# Audio_Power.net
KiCad netlist of a schematic drawn in Altium Designer
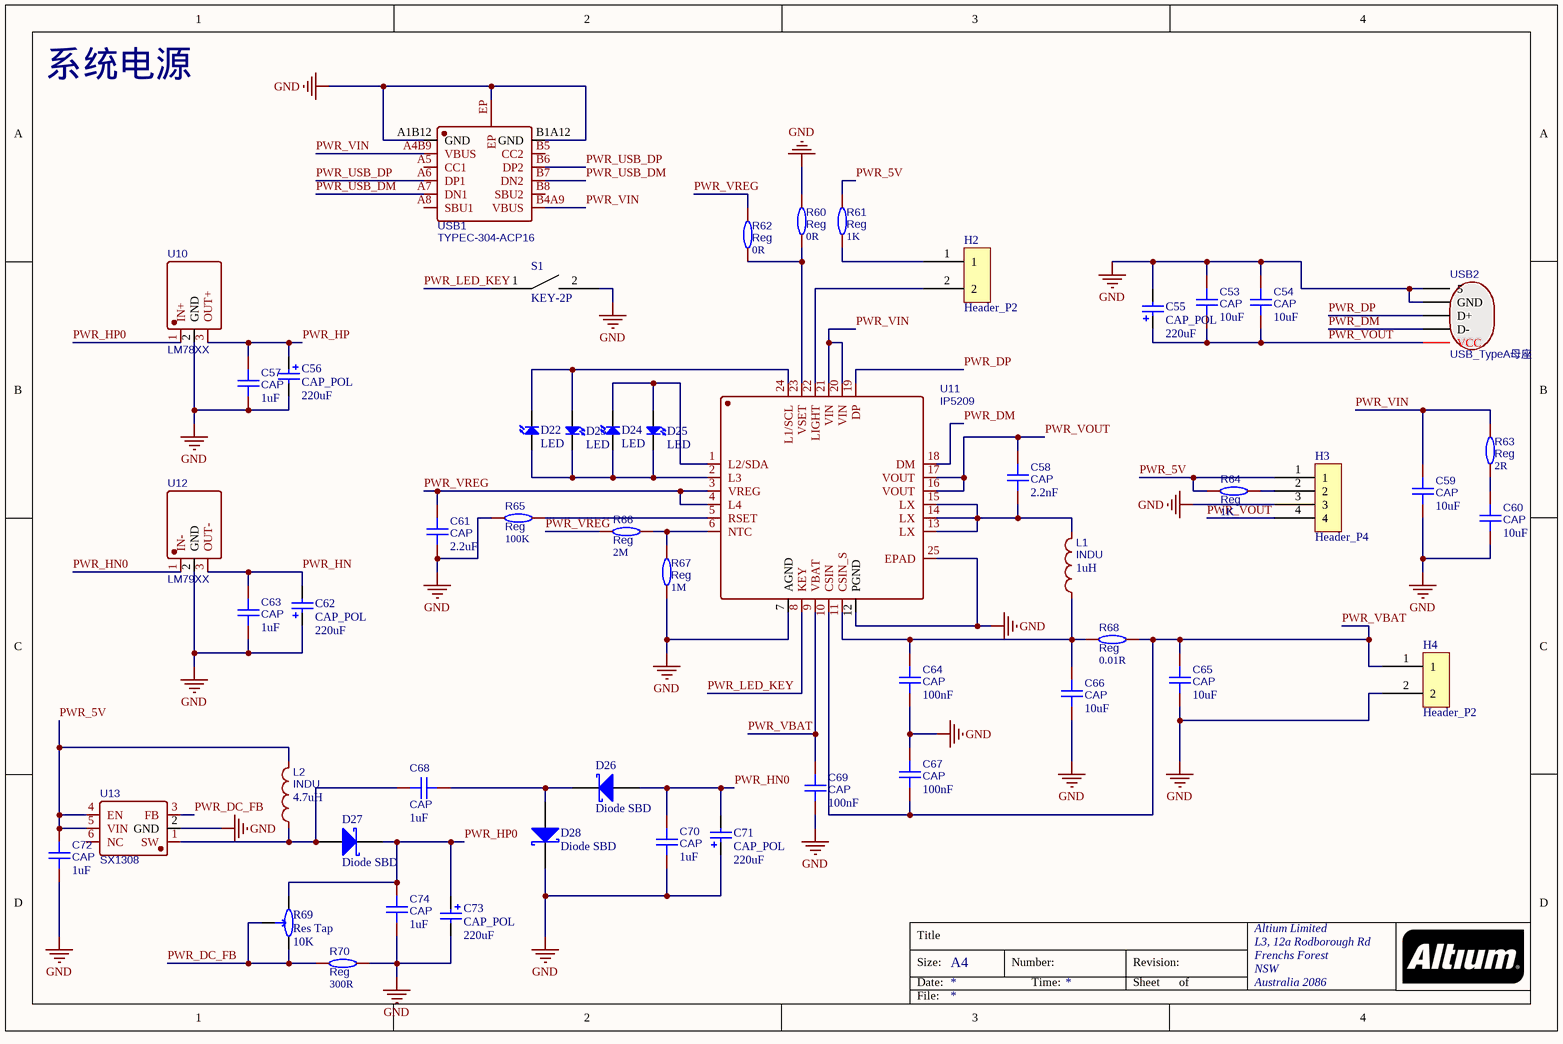
[diagram p0: Audio_Power.SchDoc]

(export (version "E")
  (design (tool "Eeschema 10.0.6"))
  (components
    (comp (ref "C53")
      (value "CAP")
      (footprint "C0603")
      (description "Cap")
      (fields
        (field (name "BOM_SUPPLIER PART") "C302008")
        (field (name "BOM_MANUFACTURER PART") "0603B103K101CT")
        (field (name "ALTIUM_VALUE") "10uF")
        (field (name "CONTRIBUTOR") "LCSC")
      )
      (libsource (lib "Levent_lib") (part "CAP"))
    )
    (comp (ref "C54")
      (value "CAP")
      (footprint "C0603")
      (description "Cap")
      (fields
        (field (name "BOM_SUPPLIER PART") "C302008")
        (field (name "BOM_MANUFACTURER PART") "0603B103K101CT")
        (field (name "ALTIUM_VALUE") "10uF")
        (field (name "CONTRIBUTOR") "LCSC")
      )
      (libsource (lib "Levent_lib") (part "CAP"))
    )
    (comp (ref "C55")
      (value "CAP_POL")
      (footprint "CAP_SMD_6.3mm")
      (description "极性电容")
      (fields (field (name "ALTIUM_VALUE") "220uF"))
      (libsource (lib "Levent_lib") (part "CAP_POL"))
    )
    (comp (ref "C56")
      (value "CAP_POL")
      (footprint "CAP_SMD_6.3mm")
      (description "极性电容")
      (fields (field (name "ALTIUM_VALUE") "220uF"))
      (libsource (lib "Levent_lib") (part "CAP_POL"))
    )
    (comp (ref "C57")
      (value "CAP")
      (footprint "C0603")
      (description "Cap")
      (fields
        (field (name "BOM_SUPPLIER PART") "C302008")
        (field (name "BOM_MANUFACTURER PART") "0603B103K101CT")
        (field (name "ALTIUM_VALUE") "1uF")
        (field (name "CONTRIBUTOR") "LCSC")
      )
      (libsource (lib "Levent_lib") (part "CAP"))
    )
    (comp (ref "C58")
      (value "CAP")
      (footprint "C0603")
      (description "Cap")
      (fields
        (field (name "BOM_SUPPLIER PART") "C302008")
        (field (name "BOM_MANUFACTURER PART") "0603B103K101CT")
        (field (name "ALTIUM_VALUE") "2.2nF")
        (field (name "CONTRIBUTOR") "LCSC")
      )
      (libsource (lib "Levent_lib") (part "CAP"))
    )
    (comp (ref "C59")
      (value "CAP")
      (footprint "C0603")
      (description "Cap")
      (fields
        (field (name "BOM_SUPPLIER PART") "C302008")
        (field (name "BOM_MANUFACTURER PART") "0603B103K101CT")
        (field (name "ALTIUM_VALUE") "10uF")
        (field (name "CONTRIBUTOR") "LCSC")
      )
      (libsource (lib "Levent_lib") (part "CAP"))
    )
    (comp (ref "C60")
      (value "CAP")
      (footprint "C0603")
      (description "Cap")
      (fields
        (field (name "BOM_SUPPLIER PART") "C302008")
        (field (name "BOM_MANUFACTURER PART") "0603B103K101CT")
        (field (name "ALTIUM_VALUE") "10uF")
        (field (name "CONTRIBUTOR") "LCSC")
      )
      (libsource (lib "Levent_lib") (part "CAP"))
    )
    (comp (ref "C61")
      (value "CAP")
      (footprint "C0603")
      (description "Cap")
      (fields
        (field (name "BOM_SUPPLIER PART") "C302008")
        (field (name "BOM_MANUFACTURER PART") "0603B103K101CT")
        (field (name "ALTIUM_VALUE") "2.2uF")
        (field (name "CONTRIBUTOR") "LCSC")
      )
      (libsource (lib "Levent_lib") (part "CAP"))
    )
    (comp (ref "C62")
      (value "CAP_POL")
      (footprint "CAP_SMD_6.3mm")
      (description "极性电容")
      (fields (field (name "ALTIUM_VALUE") "220uF"))
      (libsource (lib "Levent_lib") (part "CAP_POL"))
    )
    (comp (ref "C63")
      (value "CAP")
      (footprint "C0603")
      (description "Cap")
      (fields
        (field (name "BOM_SUPPLIER PART") "C302008")
        (field (name "BOM_MANUFACTURER PART") "0603B103K101CT")
        (field (name "ALTIUM_VALUE") "1uF")
        (field (name "CONTRIBUTOR") "LCSC")
      )
      (libsource (lib "Levent_lib") (part "CAP"))
    )
    (comp (ref "C64")
      (value "CAP")
      (footprint "C0603")
      (description "Cap")
      (fields
        (field (name "BOM_SUPPLIER PART") "C302008")
        (field (name "BOM_MANUFACTURER PART") "0603B103K101CT")
        (field (name "ALTIUM_VALUE") "100nF")
        (field (name "CONTRIBUTOR") "LCSC")
      )
      (libsource (lib "Levent_lib") (part "CAP"))
    )
    (comp (ref "C65")
      (value "CAP")
      (footprint "C0603")
      (description "Cap")
      (fields
        (field (name "BOM_SUPPLIER PART") "C302008")
        (field (name "BOM_MANUFACTURER PART") "0603B103K101CT")
        (field (name "ALTIUM_VALUE") "10uF")
        (field (name "CONTRIBUTOR") "LCSC")
      )
      (libsource (lib "Levent_lib") (part "CAP"))
    )
    (comp (ref "C66")
      (value "CAP")
      (footprint "C0603")
      (description "Cap")
      (fields
        (field (name "BOM_SUPPLIER PART") "C302008")
        (field (name "BOM_MANUFACTURER PART") "0603B103K101CT")
        (field (name "ALTIUM_VALUE") "10uF")
        (field (name "CONTRIBUTOR") "LCSC")
      )
      (libsource (lib "Levent_lib") (part "CAP"))
    )
    (comp (ref "C67")
      (value "CAP")
      (footprint "C0603")
      (description "Cap")
      (fields
        (field (name "BOM_SUPPLIER PART") "C302008")
        (field (name "BOM_MANUFACTURER PART") "0603B103K101CT")
        (field (name "ALTIUM_VALUE") "100nF")
        (field (name "CONTRIBUTOR") "LCSC")
      )
      (libsource (lib "Levent_lib") (part "CAP"))
    )
    (comp (ref "C68")
      (value "CAP")
      (footprint "C0603")
      (description "Cap")
      (fields
        (field (name "BOM_SUPPLIER PART") "C302008")
        (field (name "BOM_MANUFACTURER PART") "0603B103K101CT")
        (field (name "ALTIUM_VALUE") "1uF")
        (field (name "CONTRIBUTOR") "LCSC")
      )
      (libsource (lib "Levent_lib") (part "CAP"))
    )
    (comp (ref "C69")
      (value "CAP")
      (footprint "C0603")
      (description "Cap")
      (fields
        (field (name "BOM_SUPPLIER PART") "C302008")
        (field (name "BOM_MANUFACTURER PART") "0603B103K101CT")
        (field (name "ALTIUM_VALUE") "100nF")
        (field (name "CONTRIBUTOR") "LCSC")
      )
      (libsource (lib "Levent_lib") (part "CAP"))
    )
    (comp (ref "C70")
      (value "CAP")
      (footprint "C0603")
      (description "Cap")
      (fields
        (field (name "BOM_SUPPLIER PART") "C302008")
        (field (name "BOM_MANUFACTURER PART") "0603B103K101CT")
        (field (name "ALTIUM_VALUE") "1uF")
        (field (name "CONTRIBUTOR") "LCSC")
      )
      (libsource (lib "Levent_lib") (part "CAP"))
    )
    (comp (ref "C71")
      (value "CAP_POL")
      (footprint "CAP_SMD_6.3mm")
      (description "极性电容")
      (fields (field (name "ALTIUM_VALUE") "220uF"))
      (libsource (lib "Levent_lib") (part "CAP_POL"))
    )
    (comp (ref "C72")
      (value "CAP")
      (footprint "C0603")
      (description "Cap")
      (fields
        (field (name "BOM_SUPPLIER PART") "C302008")
        (field (name "BOM_MANUFACTURER PART") "0603B103K101CT")
        (field (name "ALTIUM_VALUE") "1uF")
        (field (name "CONTRIBUTOR") "LCSC")
      )
      (libsource (lib "Levent_lib") (part "CAP"))
    )
    (comp (ref "C73")
      (value "CAP_POL")
      (footprint "CAP_SMD_6.3mm")
      (description "极性电容")
      (fields (field (name "ALTIUM_VALUE") "220uF"))
      (libsource (lib "Levent_lib") (part "CAP_POL"))
    )
    (comp (ref "C74")
      (value "CAP")
      (footprint "C0603")
      (description "Cap")
      (fields
        (field (name "BOM_SUPPLIER PART") "C302008")
        (field (name "BOM_MANUFACTURER PART") "0603B103K101CT")
        (field (name "ALTIUM_VALUE") "1uF")
        (field (name "CONTRIBUTOR") "LCSC")
      )
      (libsource (lib "Levent_lib") (part "CAP"))
    )
    (comp (ref "D22")
      (value "LED")
      (footprint "LED0603_Side")
      (fields (field (name "PUBLISHER") "Altium Limited"))
      (libsource (lib "Levent_lib") (part "LED0"))
    )
    (comp (ref "D23")
      (value "LED")
      (footprint "LED0603_Side")
      (fields (field (name "PUBLISHER") "Altium Limited"))
      (libsource (lib "Levent_lib") (part "LED0"))
    )
    (comp (ref "D24")
      (value "LED")
      (footprint "LED0603_Side")
      (fields (field (name "PUBLISHER") "Altium Limited"))
      (libsource (lib "Levent_lib") (part "LED0"))
    )
    (comp (ref "D25")
      (value "LED")
      (footprint "LED0603_Side")
      (fields (field (name "PUBLISHER") "Altium Limited"))
      (libsource (lib "Levent_lib") (part "LED0"))
    )
    (comp (ref "D26")
      (value "Diode SBD")
      (footprint "SMA_L4.3")
      (description "Schottky Rectifier")
      (fields (field (name "PUBLISHER") "Altium Limited"))
      (libsource (lib "Levent_lib") (part "Diode SBD"))
    )
    (comp (ref "D27")
      (value "Diode SBD")
      (footprint "SMA_L4.3")
      (description "Schottky Rectifier")
      (fields (field (name "PUBLISHER") "Altium Limited"))
      (libsource (lib "Levent_lib") (part "Diode SBD"))
    )
    (comp (ref "D28")
      (value "Diode SBD")
      (footprint "SMA_L4.3")
      (description "Schottky Rectifier")
      (fields (field (name "PUBLISHER") "Altium Limited"))
      (libsource (lib "Levent_lib") (part "Diode SBD"))
    )
    (comp (ref "H2")
      (value "Header_P2")
      (footprint "H_2.54_P2")
      (description "2Pin排针")
      (libsource (lib "Levent_lib") (part "Header_P2"))
    )
    (comp (ref "H3")
      (value "Header_P4")
      (footprint "H_2.54_P4")
      (description "4Pin排针")
      (libsource (lib "Levent_lib") (part "Header_P4"))
    )
    (comp (ref "H4")
      (value "Header_P2")
      (footprint "H_2.54_P2")
      (description "2Pin排针")
      (libsource (lib "Levent_lib") (part "Header_P2"))
    )
    (comp (ref "L1")
      (value "INDU")
      (footprint "SMD_L7.1")
      (description "电感")
      (fields
        (field (name "BOM_SUPPLIER PART") "C182182")
        (field (name "BOM_MANUFACTURER PART") "SLO0630H150MTT")
        (field (name "ALTIUM_VALUE") "1uH")
        (field (name "CONTRIBUTOR") "LCSC")
      )
      (libsource (lib "Levent_lib") (part "IND"))
    )
    (comp (ref "L2")
      (value "INDU")
      (footprint "SMD_L7.1")
      (description "电感")
      (fields
        (field (name "BOM_SUPPLIER PART") "C182182")
        (field (name "BOM_MANUFACTURER PART") "SLO0630H150MTT")
        (field (name "ALTIUM_VALUE") "4.7uH")
        (field (name "CONTRIBUTOR") "LCSC")
      )
      (libsource (lib "Levent_lib") (part "IND"))
    )
    (comp (ref "R60")
      (value "Reg")
      (footprint "R0603")
      (description "电阻")
      (fields
        (field (name "BOM_SUPPLIER PART") "C465721")
        (field (name "BOM_MANUFACTURER PART") "AR03BTCX1002A")
        (field (name "ALTIUM_VALUE") "0R")
        (field (name "CONTRIBUTOR") "LCSC")
      )
      (libsource (lib "Levent_lib") (part "Res"))
    )
    (comp (ref "R61")
      (value "Reg")
      (footprint "R0603")
      (description "电阻")
      (fields
        (field (name "BOM_SUPPLIER PART") "C465721")
        (field (name "BOM_MANUFACTURER PART") "AR03BTCX1002A")
        (field (name "ALTIUM_VALUE") "1K")
        (field (name "CONTRIBUTOR") "LCSC")
      )
      (libsource (lib "Levent_lib") (part "Res"))
    )
    (comp (ref "R62")
      (value "Reg")
      (footprint "R0603")
      (description "电阻")
      (fields
        (field (name "BOM_SUPPLIER PART") "C465721")
        (field (name "BOM_MANUFACTURER PART") "AR03BTCX1002A")
        (field (name "ALTIUM_VALUE") "0R")
        (field (name "CONTRIBUTOR") "LCSC")
      )
      (libsource (lib "Levent_lib") (part "Res"))
    )
    (comp (ref "R63")
      (value "Reg")
      (footprint "R0603")
      (description "电阻")
      (fields
        (field (name "BOM_SUPPLIER PART") "C465721")
        (field (name "BOM_MANUFACTURER PART") "AR03BTCX1002A")
        (field (name "ALTIUM_VALUE") "2R")
        (field (name "CONTRIBUTOR") "LCSC")
      )
      (libsource (lib "Levent_lib") (part "Res"))
    )
    (comp (ref "R64")
      (value "Reg")
      (footprint "R0603")
      (description "电阻")
      (fields
        (field (name "BOM_SUPPLIER PART") "C465721")
        (field (name "BOM_MANUFACTURER PART") "AR03BTCX1002A")
        (field (name "ALTIUM_VALUE") "1K")
        (field (name "CONTRIBUTOR") "LCSC")
      )
      (libsource (lib "Levent_lib") (part "Res"))
    )
    (comp (ref "R65")
      (value "Reg")
      (footprint "R0603")
      (description "电阻")
      (fields
        (field (name "BOM_SUPPLIER PART") "C465721")
        (field (name "BOM_MANUFACTURER PART") "AR03BTCX1002A")
        (field (name "ALTIUM_VALUE") "100K")
        (field (name "CONTRIBUTOR") "LCSC")
      )
      (libsource (lib "Levent_lib") (part "Res"))
    )
    (comp (ref "R66")
      (value "Reg")
      (footprint "R0603")
      (description "电阻")
      (fields
        (field (name "BOM_SUPPLIER PART") "C465721")
        (field (name "BOM_MANUFACTURER PART") "AR03BTCX1002A")
        (field (name "ALTIUM_VALUE") "2M")
        (field (name "CONTRIBUTOR") "LCSC")
      )
      (libsource (lib "Levent_lib") (part "Res"))
    )
    (comp (ref "R67")
      (value "Reg")
      (footprint "R0603")
      (description "电阻")
      (fields
        (field (name "BOM_SUPPLIER PART") "C465721")
        (field (name "BOM_MANUFACTURER PART") "AR03BTCX1002A")
        (field (name "ALTIUM_VALUE") "1M")
        (field (name "CONTRIBUTOR") "LCSC")
      )
      (libsource (lib "Levent_lib") (part "Res"))
    )
    (comp (ref "R68")
      (value "Reg")
      (footprint "R1206")
      (description "电阻")
      (fields
        (field (name "BOM_SUPPLIER PART") "C465721")
        (field (name "BOM_MANUFACTURER PART") "AR03BTCX1002A")
        (field (name "ALTIUM_VALUE") "0.01R")
        (field (name "CONTRIBUTOR") "LCSC")
      )
      (libsource (lib "Levent_lib") (part "Res"))
    )
    (comp (ref "R69")
      (value "Res Tap")
      (footprint "RES_TAP_HOR")
      (description "可调电阻")
      (fields (field (name "ALTIUM_VALUE") "10K") (field (name "PUBLISHER") "Altium Limited"))
      (libsource (lib "Levent_lib") (part "Res Tap"))
    )
    (comp (ref "R70")
      (value "Reg")
      (footprint "R0603")
      (description "电阻")
      (fields
        (field (name "BOM_SUPPLIER PART") "C465721")
        (field (name "BOM_MANUFACTURER PART") "AR03BTCX1002A")
        (field (name "ALTIUM_VALUE") "300R")
        (field (name "CONTRIBUTOR") "LCSC")
      )
      (libsource (lib "Levent_lib") (part "Res"))
    )
    (comp (ref "S1")
      (value "KEY-2P")
      (footprint "KEY_SOT_P2")
      (description "KEY-2Pp")
      (libsource (lib "Levent_lib") (part "KEY_2P"))
    )
    (comp (ref "U10")
      (value "LM78XX")
      (footprint "TO-220-3_2.54")
      (description "三端稳压(正电压)")
      (fields
        (field (name "BOM_SUPPLIER PART") "C2902509")
        (field (name "BOM_MANUFACTURER PART") "LM7812T")
        (field (name "CONTRIBUTOR") "LCSC")
      )
      (libsource (lib "Levent_lib") (part "LM78XX"))
    )
    (comp (ref "U11")
      (value "IP5209")
      (footprint "QFN-24")
      (description "USB充电宝")
      (fields (field (name "BOM_SUPPLIER PART") "C181695") (field (name "CONTRIBUTOR") "LCSC"))
      (libsource (lib "Levent_lib") (part "IP5209"))
    )
    (comp (ref "U12")
      (value "LM79XX")
      (footprint "TO-220-3_2.54")
      (description "三端稳压(负电压)")
      (fields
        (field (name "BOM_SUPPLIER PART") "C2902509")
        (field (name "BOM_MANUFACTURER PART") "LM7812T")
        (field (name "CONTRIBUTOR") "LCSC")
      )
      (libsource (lib "Levent_lib") (part "LM79XX"))
    )
    (comp (ref "U13")
      (value "SX1308")
      (footprint "SOT-23-6")
      (description "升压PWM")
      (fields (field (name "BOM_SUPPLIER PART") "C78162"))
      (libsource (lib "Levent_lib") (part "SX1308"))
    )
    (comp (ref "USB1")
      (value "TYPEC-304-ACP16")
      (footprint "USB-C-SMD_TYPE-C-16P")
      (description "全引脚USB TYPEC母座")
      (fields (field (name "BOM_SUPPLIER PART") "C2982555") (field (name "CONTRIBUTOR") "LCSC"))
      (libsource (lib "Levent_lib") (part "USB_TYPEC_12P"))
    )
    (comp (ref "USB2")
      (value "USB_TypeA母座")
      (footprint "USB_TYPEA-SMD")
      (fields
        (field (name "BOM_MANUFACTURER PART") "YJ-USB-AF-SMT-01")
        (field (name "BOM_SUPPLIER PART") "C8328")
      )
      (libsource (lib "Levent_lib") (part "USB-TYPEA"))
    )
  )
  (nets
    (net (code "1") (name "/PWR_5V") (class "Default")
      (node (ref "C72") (pin "1") (pinfunction "1_1") (pintype "passive"))
      (node (ref "H3") (pin "1") (pinfunction "1_1") (pintype "passive"))
      (node (ref "L2") (pin "2") (pinfunction "2_2") (pintype "passive"))
      (node (ref "R61") (pin "2") (pinfunction "2_2") (pintype "passive"))
      (node (ref "R64") (pin "1") (pinfunction "1_1") (pintype "passive"))
      (node (ref "U13") (pin "4") (pinfunction "EN_4") (pintype "passive"))
      (node (ref "U13") (pin "5") (pinfunction "VIN_5") (pintype "passive"))
    )
    (net (code "2") (name "/PWR_DC_FB") (class "Default")
      (node (ref "R69") (pin "1") (pinfunction "A_1") (pintype "passive"))
      (node (ref "R69") (pin "3") (pinfunction "TAP_3") (pintype "passive"))
      (node (ref "R70") (pin "1") (pinfunction "1_1") (pintype "passive"))
      (node (ref "U13") (pin "3") (pinfunction "FB_3") (pintype "passive"))
    )
    (net (code "3") (name "/PWR_DM") (class "Default")
      (node (ref "U11") (pin "18") (pinfunction "DM_18") (pintype "passive"))
      (node (ref "USB2") (pin "2") (pinfunction "D-_2") (pintype "passive"))
    )
    (net (code "4") (name "/PWR_DP") (class "Default")
      (node (ref "U11") (pin "19") (pinfunction "DP_19") (pintype "passive"))
      (node (ref "USB2") (pin "3") (pinfunction "D+_3") (pintype "passive"))
    )
    (net (code "5") (name "/PWR_HN") (class "Default")
      (node (ref "C62") (pin "2") (pinfunction "2_2") (pintype "passive"))
      (node (ref "C63") (pin "1") (pinfunction "1_1") (pintype "passive"))
      (node (ref "U12") (pin "3") (pinfunction "OUT-_3") (pintype "passive"))
    )
    (net (code "6") (name "/PWR_HN0") (class "Default")
      (node (ref "C70") (pin "1") (pinfunction "1_1") (pintype "passive"))
      (node (ref "C71") (pin "2") (pinfunction "2_2") (pintype "passive"))
      (node (ref "D26") (pin "2") (pinfunction "A_2") (pintype "passive"))
      (node (ref "U12") (pin "1") (pinfunction "IN-_1") (pintype "passive"))
    )
    (net (code "7") (name "/PWR_HP") (class "Default")
      (node (ref "C56") (pin "1") (pinfunction "1_1") (pintype "passive"))
      (node (ref "C57") (pin "1") (pinfunction "1_1") (pintype "passive"))
      (node (ref "U10") (pin "3") (pinfunction "OUT+_3") (pintype "passive"))
    )
    (net (code "8") (name "/PWR_HP0") (class "Default")
      (node (ref "C73") (pin "1") (pinfunction "1_1") (pintype "passive"))
      (node (ref "C74") (pin "1") (pinfunction "1_1") (pintype "passive"))
      (node (ref "D27") (pin "1") (pinfunction "K_1") (pintype "passive"))
      (node (ref "R69") (pin "2") (pinfunction "B_2") (pintype "passive"))
      (node (ref "U10") (pin "1") (pinfunction "IN+_1") (pintype "passive"))
    )
    (net (code "9") (name "/PWR_LED_KEY") (class "Default")
      (node (ref "S1") (pin "1") (pinfunction "1_1") (pintype "passive"))
      (node (ref "U11") (pin "8") (pinfunction "KEY_8") (pintype "passive"))
    )
    (net (code "10") (name "/PWR_USB_DM") (class "Default")
      (node (ref "USB1") (pin "A7") (pinfunction "DN1_A7") (pintype "passive"))
      (node (ref "USB1") (pin "B7") (pinfunction "DN2_B7") (pintype "passive"))
    )
    (net (code "11") (name "/PWR_USB_DP") (class "Default")
      (node (ref "USB1") (pin "A6") (pinfunction "DP1_A6") (pintype "passive"))
      (node (ref "USB1") (pin "B6") (pinfunction "DP2_B6") (pintype "passive"))
    )
    (net (code "12") (name "/PWR_VBAT") (class "Default")
      (node (ref "C65") (pin "1") (pinfunction "1_1") (pintype "passive"))
      (node (ref "C67") (pin "2") (pinfunction "2_2") (pintype "passive"))
      (node (ref "C69") (pin "1") (pinfunction "1_1") (pintype "passive"))
      (node (ref "H4") (pin "1") (pinfunction "1_1") (pintype "passive"))
      (node (ref "R68") (pin "2") (pinfunction "2_2") (pintype "passive"))
      (node (ref "U11") (pin "10") (pinfunction "CSIN_10") (pintype "passive"))
      (node (ref "U11") (pin "9") (pinfunction "VBAT_9") (pintype "passive"))
    )
    (net (code "13") (name "/PWR_VIN") (class "Default")
      (node (ref "C59") (pin "1") (pinfunction "1_1") (pintype "passive"))
      (node (ref "R63") (pin "2") (pinfunction "2_2") (pintype "passive"))
      (node (ref "U11") (pin "20") (pinfunction "VIN_20") (pintype "passive"))
      (node (ref "U11") (pin "21") (pinfunction "VIN_21") (pintype "passive"))
      (node (ref "USB1") (pin "A4B9") (pinfunction "VBUS_A4B9") (pintype "passive"))
      (node (ref "USB1") (pin "B4A9") (pinfunction "VBUS_B4A9") (pintype "passive"))
    )
    (net (code "14") (name "/PWR_VOUT") (class "Default")
      (node (ref "C53") (pin "2") (pinfunction "2_2") (pintype "passive"))
      (node (ref "C54") (pin "2") (pinfunction "2_2") (pintype "passive"))
      (node (ref "C55") (pin "1") (pinfunction "1_1") (pintype "passive"))
      (node (ref "C58") (pin "1") (pinfunction "1_1") (pintype "passive"))
      (node (ref "H3") (pin "4") (pinfunction "4_4") (pintype "passive"))
      (node (ref "U11") (pin "16") (pinfunction "VOUT_16") (pintype "passive"))
      (node (ref "U11") (pin "17") (pinfunction "VOUT_17") (pintype "passive"))
      (node (ref "USB2") (pin "1") (pinfunction "VCC_1") (pintype "passive"))
    )
    (net (code "15") (name "/PWR_VREG") (class "Default")
      (node (ref "C61") (pin "1") (pinfunction "1_1") (pintype "passive"))
      (node (ref "R62") (pin "2") (pinfunction "2_2") (pintype "passive"))
      (node (ref "R66") (pin "2") (pinfunction "2_2") (pintype "passive"))
      (node (ref "U11") (pin "3") (pinfunction "VREG_3") (pintype "passive"))
      (node (ref "U11") (pin "4") (pinfunction "L4_4") (pintype "passive"))
    )
    (net (code "16") (name "GND") (class "Default")
      (node (ref "C53") (pin "1") (pinfunction "1_1") (pintype "passive"))
      (node (ref "C54") (pin "1") (pinfunction "1_1") (pintype "passive"))
      (node (ref "C55") (pin "2") (pinfunction "2_2") (pintype "passive"))
      (node (ref "C56") (pin "2") (pinfunction "2_2") (pintype "passive"))
      (node (ref "C57") (pin "2") (pinfunction "2_2") (pintype "passive"))
      (node (ref "C59") (pin "2") (pinfunction "2_2") (pintype "passive"))
      (node (ref "C60") (pin "2") (pinfunction "2_2") (pintype "passive"))
      (node (ref "C61") (pin "2") (pinfunction "2_2") (pintype "passive"))
      (node (ref "C62") (pin "1") (pinfunction "1_1") (pintype "passive"))
      (node (ref "C63") (pin "2") (pinfunction "2_2") (pintype "passive"))
      (node (ref "C64") (pin "2") (pinfunction "2_2") (pintype "passive"))
      (node (ref "C65") (pin "2") (pinfunction "2_2") (pintype "passive"))
      (node (ref "C66") (pin "2") (pinfunction "2_2") (pintype "passive"))
      (node (ref "C67") (pin "1") (pinfunction "1_1") (pintype "passive"))
      (node (ref "C69") (pin "2") (pinfunction "2_2") (pintype "passive"))
      (node (ref "C70") (pin "2") (pinfunction "2_2") (pintype "passive"))
      (node (ref "C71") (pin "1") (pinfunction "1_1") (pintype "passive"))
      (node (ref "C72") (pin "2") (pinfunction "2_2") (pintype "passive"))
      (node (ref "C73") (pin "2") (pinfunction "2_2") (pintype "passive"))
      (node (ref "C74") (pin "2") (pinfunction "2_2") (pintype "passive"))
      (node (ref "D28") (pin "1") (pinfunction "K_1") (pintype "passive"))
      (node (ref "H3") (pin "3") (pinfunction "3_3") (pintype "passive"))
      (node (ref "H4") (pin "2") (pinfunction "2_2") (pintype "passive"))
      (node (ref "R60") (pin "2") (pinfunction "2_2") (pintype "passive"))
      (node (ref "R65") (pin "2") (pinfunction "2_2") (pintype "passive"))
      (node (ref "R67") (pin "2") (pinfunction "2_2") (pintype "passive"))
      (node (ref "R70") (pin "2") (pinfunction "2_2") (pintype "passive"))
      (node (ref "S1") (pin "2") (pinfunction "2_2") (pintype "passive"))
      (node (ref "U10") (pin "2") (pinfunction "GND_2") (pintype "passive"))
      (node (ref "U11") (pin "12") (pinfunction "PGND_12") (pintype "passive"))
      (node (ref "U11") (pin "25") (pinfunction "EPAD_25") (pintype "passive"))
      (node (ref "U11") (pin "7") (pinfunction "AGND_7") (pintype "passive"))
      (node (ref "U12") (pin "2") (pinfunction "GND_2") (pintype "passive"))
      (node (ref "U13") (pin "2") (pinfunction "GND_2") (pintype "passive"))
      (node (ref "USB1") (pin "A1B12") (pinfunction "GND_A1B12") (pintype "passive"))
      (node (ref "USB1") (pin "B1A12") (pinfunction "GND_B1A12") (pintype "passive"))
      (node (ref "USB1") (pin "EP") (pinfunction "EP_EP") (pintype "passive"))
      (node (ref "USB2") (pin "4") (pinfunction "GND_4") (pintype "passive"))
      (node (ref "USB2") (pin "5") (pinfunction "5_5") (pintype "passive"))
    )
    (net (code "17") (name "Net-(C58-Pad2)") (class "Default")
      (node (ref "C58") (pin "2") (pinfunction "2_2") (pintype "passive"))
      (node (ref "L1") (pin "2") (pinfunction "2_2") (pintype "passive"))
      (node (ref "U11") (pin "13") (pinfunction "LX_13") (pintype "passive"))
      (node (ref "U11") (pin "14") (pinfunction "LX_14") (pintype "passive"))
      (node (ref "U11") (pin "15") (pinfunction "LX_15") (pintype "passive"))
    )
    (net (code "18") (name "Net-(C60-Pad1)") (class "Default")
      (node (ref "C60") (pin "1") (pinfunction "1_1") (pintype "passive"))
      (node (ref "R63") (pin "1") (pinfunction "1_1") (pintype "passive"))
    )
    (net (code "19") (name "Net-(D22-A)") (class "Default")
      (node (ref "D22") (pin "2") (pinfunction "A_2") (pintype "passive"))
      (node (ref "D23") (pin "1") (pinfunction "K_1") (pintype "passive"))
      (node (ref "D24") (pin "2") (pinfunction "A_2") (pintype "passive"))
      (node (ref "D25") (pin "1") (pinfunction "K_1") (pintype "passive"))
      (node (ref "U11") (pin "2") (pinfunction "L3_2") (pintype "passive"))
    )
    (net (code "20") (name "Net-(D22-K)") (class "Default")
      (node (ref "D22") (pin "1") (pinfunction "K_1") (pintype "passive"))
      (node (ref "D23") (pin "2") (pinfunction "A_2") (pintype "passive"))
      (node (ref "U11") (pin "24") (pinfunction "L1/SCL_24") (pintype "passive"))
    )
    (net (code "21") (name "Net-(D24-K)") (class "Default")
      (node (ref "D24") (pin "1") (pinfunction "K_1") (pintype "passive"))
      (node (ref "D25") (pin "2") (pinfunction "A_2") (pintype "passive"))
      (node (ref "U11") (pin "1") (pinfunction "L2/SDA_1") (pintype "passive"))
    )
    (net (code "22") (name "Net-(D26-K)") (class "Default")
      (node (ref "C68") (pin "2") (pinfunction "2_2") (pintype "passive"))
      (node (ref "D26") (pin "1") (pinfunction "K_1") (pintype "passive"))
      (node (ref "D28") (pin "2") (pinfunction "A_2") (pintype "passive"))
    )
    (net (code "23") (name "Net-(D27-A)") (class "Default")
      (node (ref "C68") (pin "1") (pinfunction "1_1") (pintype "passive"))
      (node (ref "D27") (pin "2") (pinfunction "A_2") (pintype "passive"))
      (node (ref "L2") (pin "1") (pinfunction "1_1") (pintype "passive"))
      (node (ref "U13") (pin "1") (pinfunction "SW_1") (pintype "passive"))
    )
    (net (code "24") (name "Net-(H2-Pad1)") (class "Default")
      (node (ref "H2") (pin "1") (pinfunction "1_1") (pintype "passive"))
      (node (ref "R61") (pin "1") (pinfunction "1_1") (pintype "passive"))
    )
    (net (code "25") (name "Net-(H3-Pad2)") (class "Default")
      (node (ref "H3") (pin "2") (pinfunction "2_2") (pintype "passive"))
      (node (ref "R64") (pin "2") (pinfunction "2_2") (pintype "passive"))
    )
    (net (code "26") (name "Net-(U11-CSIN_S)") (class "Default")
      (node (ref "C64") (pin "1") (pinfunction "1_1") (pintype "passive"))
      (node (ref "C66") (pin "1") (pinfunction "1_1") (pintype "passive"))
      (node (ref "L1") (pin "1") (pinfunction "1_1") (pintype "passive"))
      (node (ref "R68") (pin "1") (pinfunction "1_1") (pintype "passive"))
      (node (ref "U11") (pin "11") (pinfunction "CSIN_S_11") (pintype "passive"))
    )
    (net (code "27") (name "Net-(U11-LIGHT)") (class "Default")
      (node (ref "H2") (pin "2") (pinfunction "2_2") (pintype "passive"))
      (node (ref "U11") (pin "22") (pinfunction "LIGHT_22") (pintype "passive"))
    )
    (net (code "28") (name "Net-(U11-NTC)") (class "Default")
      (node (ref "R66") (pin "1") (pinfunction "1_1") (pintype "passive"))
      (node (ref "R67") (pin "1") (pinfunction "1_1") (pintype "passive"))
      (node (ref "U11") (pin "6") (pinfunction "NTC_6") (pintype "passive"))
    )
    (net (code "29") (name "Net-(U11-RSET)") (class "Default")
      (node (ref "R65") (pin "1") (pinfunction "1_1") (pintype "passive"))
      (node (ref "U11") (pin "5") (pinfunction "RSET_5") (pintype "passive"))
    )
    (net (code "30") (name "Net-(U11-VSET)") (class "Default")
      (node (ref "R60") (pin "1") (pinfunction "1_1") (pintype "passive"))
      (node (ref "R62") (pin "1") (pinfunction "1_1") (pintype "passive"))
      (node (ref "U11") (pin "23") (pinfunction "VSET_23") (pintype "passive"))
    )
    (net (code "31") (name "unconnected-(U13-NC-Pad6)") (class "Default")
      (node (ref "U13") (pin "6") (pinfunction "NC_6") (pintype "passive"))
    )
    (net (code "32") (name "unconnected-(USB1-CC1-PadA5)") (class "Default")
      (node (ref "USB1") (pin "A5") (pinfunction "CC1_A5") (pintype "passive"))
    )
    (net (code "33") (name "unconnected-(USB1-CC2-PadB5)") (class "Default")
      (node (ref "USB1") (pin "B5") (pinfunction "CC2_B5") (pintype "passive"))
    )
    (net (code "34") (name "unconnected-(USB1-SBU1-PadA8)") (class "Default")
      (node (ref "USB1") (pin "A8") (pinfunction "SBU1_A8") (pintype "passive"))
    )
    (net (code "35") (name "unconnected-(USB1-SBU2-PadB8)") (class "Default")
      (node (ref "USB1") (pin "B8") (pinfunction "SBU2_B8") (pintype "passive"))
    )
  )
)
